# UWB3000.net
KiCad netlist of a schematic drawn in Altium Designer
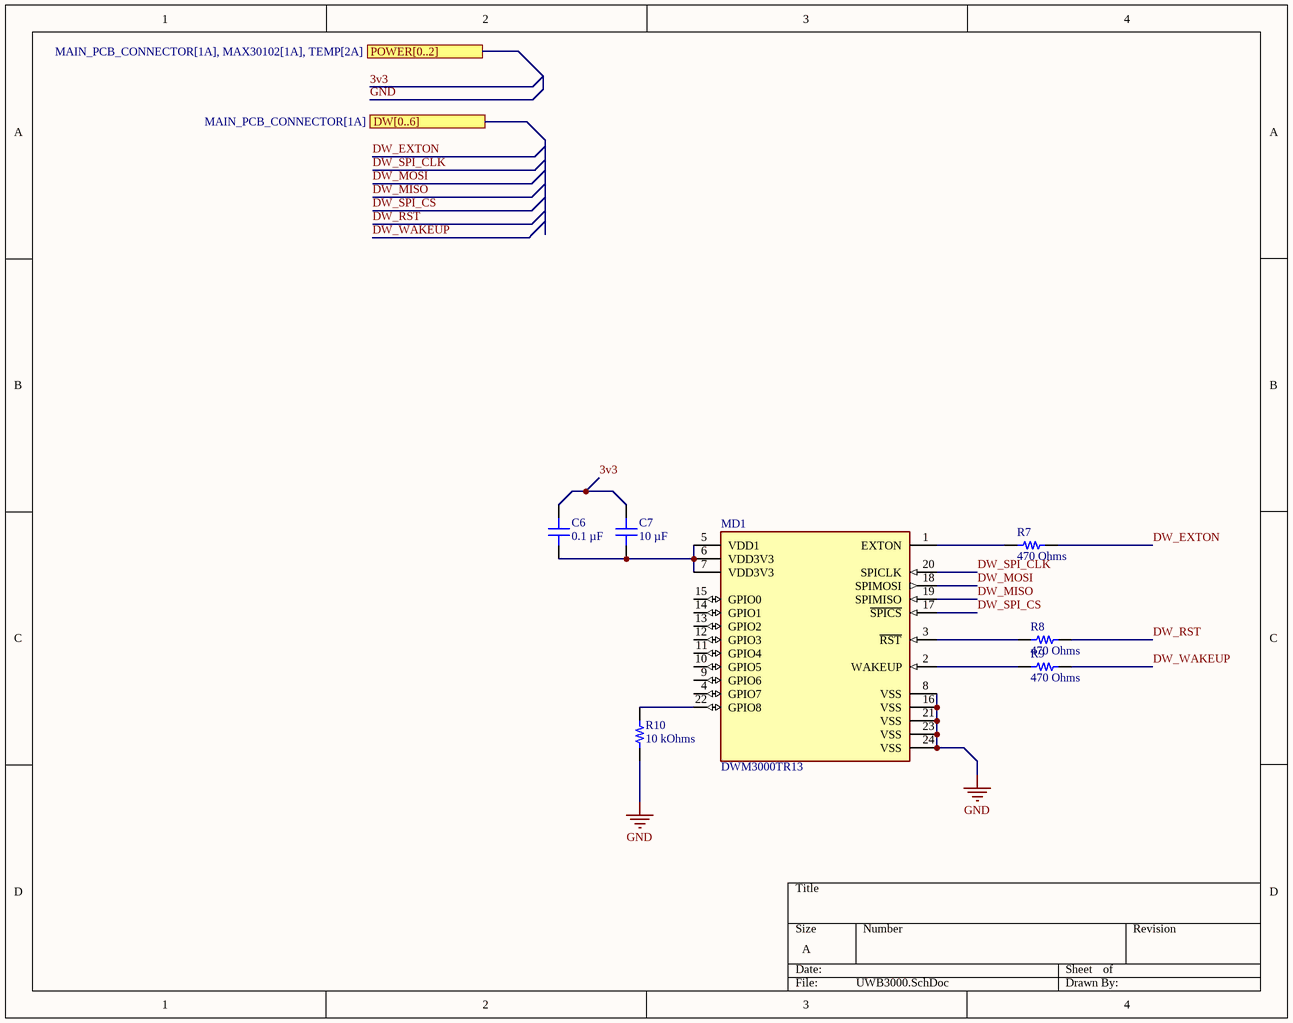
[diagram p0: UWB3000.SchDoc]

(export (version "E")
  (design (tool "Eeschema 10.0.6"))
  (components
    (comp (ref "C6")
      (value "~")
      (footprint "CAP 0402_1005")
      (description "CAP CER 0.1UF 16V X7R 0402")
      (fields
        (field (name "CAPACITANCE") "0.1 µF")
        (field (name "MANUFACTURER") "Samsung Electro-Mechanics")
        (field (name "MFR.PART #") "CL05B104KO5NNNC")
      )
      (libsource (lib "Celestial Altium Library - altium_library") (part "Capacitor"))
    )
    (comp (ref "C7")
      (value "~")
      (footprint "CAP 0402_1005")
      (description "CAP CER 10UF 6.3V X5R 0402")
      (fields
        (field (name "CAPACITANCE") "10 µF")
        (field (name "MANUFACTURER") "Samsung Electro-Mechanics")
        (field (name "MFR.PART #") "CL05A106MQ5NUNC")
      )
      (libsource (lib "Celestial Altium Library - altium_library") (part "Capacitor"))
    )
    (comp (ref "MD1")
      (value "DWM3000TR13")
      (footprint "FP-DWM3000TR13-MFG")
      (description "DWM3000 module Freq: 7.9872 GHz 6.8Mbps SPI 2.5-3.6V 8 GPIO's")
      (fields (field (name "MANUFACTURER") "Qorvo") (field (name "JLCPCB PART #") "C5299931"))
      (libsource (lib "Altium Content Vault") (part "094cfe914922597e69cd10df7811a9c"))
    )
    (comp (ref "R7")
      (value "470 Ohms")
      (footprint "RES 0402_1005")
      (description "RES 470 OHM 0.1% 1/16W 0402")
      (fields
        (field (name "MANUFACTURER") "UNI-ROYAL(Uniroyal Elec)")
        (field (name "MFR.PART #") "0402WGF4700TCE")
      )
      (libsource (lib "Celestial Altium Library - altium_library") (part "Resistor"))
    )
    (comp (ref "R8")
      (value "470 Ohms")
      (footprint "RES 0402_1005")
      (description "RES 470 OHM 0.1% 1/16W 0402")
      (fields
        (field (name "MANUFACTURER") "UNI-ROYAL(Uniroyal Elec)")
        (field (name "MFR.PART #") "0402WGF4700TCE")
      )
      (libsource (lib "Celestial Altium Library - altium_library") (part "Resistor"))
    )
    (comp (ref "R9")
      (value "470 Ohms")
      (footprint "RES 0402_1005")
      (description "RES 470 OHM 0.1% 1/16W 0402")
      (fields
        (field (name "MANUFACTURER") "UNI-ROYAL(Uniroyal Elec)")
        (field (name "MFR.PART #") "0402WGF4700TCE")
      )
      (libsource (lib "Celestial Altium Library - altium_library") (part "Resistor"))
    )
    (comp (ref "R10")
      (value "10 kOhms")
      (footprint "RES 0402_1005")
      (description "RES 10K OHM 0.1% 1/10W 0402")
      (fields (field (name "MANUFACTURER") "Ever Ohms Tech") (field (name "MFR.PART #") "TR0402D10K0Q1025Z"))
      (libsource (lib "Celestial Altium Library - altium_library") (part "Resistor"))
    )
  )
  (nets
    (net (code "11") (name "/3v3") (class "Default")
      (node (ref "C6") (pin "2") (pinfunction "2_2") (pintype "passive"))
      (node (ref "C7") (pin "2") (pinfunction "2_2") (pintype "passive"))
    )
    (net (code "13") (name "/DW_EXTON") (class "Default")
      (node (ref "R7") (pin "2") (pinfunction "2_2") (pintype "passive"))
    )
    (net (code "14") (name "/DW_MISO") (class "Default")
      (node (ref "MD1") (pin "19") (pinfunction "SPIMISO_19") (pintype "input"))
    )
    (net (code "15") (name "/DW_MOSI") (class "Default")
      (node (ref "MD1") (pin "18") (pinfunction "SPIMOSI_18") (pintype "output"))
    )
    (net (code "16") (name "/DW_RST") (class "Default")
      (node (ref "R8") (pin "2") (pinfunction "2_2") (pintype "passive"))
    )
    (net (code "17") (name "/DW_SPI_CLK") (class "Default")
      (node (ref "MD1") (pin "20") (pinfunction "SPICLK_20") (pintype "input"))
    )
    (net (code "18") (name "/DW_SPI_CS") (class "Default")
      (node (ref "MD1") (pin "17") (pinfunction "~{SPICS}_17") (pintype "input"))
    )
    (net (code "19") (name "/DW_WAKEUP") (class "Default")
      (node (ref "R9") (pin "2") (pinfunction "2_2") (pintype "passive"))
    )
    (net (code "21") (name "GND") (class "Default")
      (node (ref "MD1") (pin "16") (pinfunction "VSS_16") (pintype "power_in"))
      (node (ref "MD1") (pin "21") (pinfunction "VSS_21") (pintype "power_in"))
      (node (ref "MD1") (pin "23") (pinfunction "VSS_23") (pintype "power_in"))
      (node (ref "MD1") (pin "24") (pinfunction "VSS_24") (pintype "power_in"))
      (node (ref "MD1") (pin "8") (pinfunction "VSS_8") (pintype "power_in"))
      (node (ref "R10") (pin "1") (pinfunction "1_1") (pintype "passive"))
    )
    (net (code "22") (name "Net-(MD1-EXTON)") (class "Default")
      (node (ref "MD1") (pin "1") (pinfunction "EXTON_1") (pintype "passive"))
      (node (ref "R7") (pin "1") (pinfunction "1_1") (pintype "passive"))
    )
    (net (code "23") (name "Net-(MD1-GPIO8)") (class "Default")
      (node (ref "MD1") (pin "22") (pinfunction "GPIO8_22") (pintype "bidirectional"))
      (node (ref "R10") (pin "2") (pinfunction "2_2") (pintype "passive"))
    )
    (net (code "24") (name "Net-(MD1-VDD1)") (class "Default")
      (node (ref "C6") (pin "1") (pinfunction "1_1") (pintype "passive"))
      (node (ref "C7") (pin "1") (pinfunction "1_1") (pintype "passive"))
      (node (ref "MD1") (pin "5") (pinfunction "VDD1_5") (pintype "power_in"))
      (node (ref "MD1") (pin "6") (pinfunction "VDD3V3_6") (pintype "power_in"))
      (node (ref "MD1") (pin "7") (pinfunction "VDD3V3_7") (pintype "power_in"))
    )
    (net (code "25") (name "Net-(MD1-WAKEUP)") (class "Default")
      (node (ref "MD1") (pin "2") (pinfunction "WAKEUP_2") (pintype "input"))
      (node (ref "R9") (pin "1") (pinfunction "1_1") (pintype "passive"))
    )
    (net (code "26") (name "Net-(MD1-~{RST})") (class "Default")
      (node (ref "MD1") (pin "3") (pinfunction "~{RST}_3") (pintype "input"))
      (node (ref "R8") (pin "1") (pinfunction "1_1") (pintype "passive"))
    )
    (net (code "27") (name "unconnected-(MD1-GPIO0-Pad15)") (class "Default")
      (node (ref "MD1") (pin "15") (pinfunction "GPIO0_15") (pintype "bidirectional"))
    )
    (net (code "28") (name "unconnected-(MD1-GPIO1-Pad14)") (class "Default")
      (node (ref "MD1") (pin "14") (pinfunction "GPIO1_14") (pintype "bidirectional"))
    )
    (net (code "29") (name "unconnected-(MD1-GPIO2-Pad13)") (class "Default")
      (node (ref "MD1") (pin "13") (pinfunction "GPIO2_13") (pintype "bidirectional"))
    )
    (net (code "30") (name "unconnected-(MD1-GPIO3-Pad12)") (class "Default")
      (node (ref "MD1") (pin "12") (pinfunction "GPIO3_12") (pintype "bidirectional"))
    )
    (net (code "31") (name "unconnected-(MD1-GPIO4-Pad11)") (class "Default")
      (node (ref "MD1") (pin "11") (pinfunction "GPIO4_11") (pintype "bidirectional"))
    )
    (net (code "32") (name "unconnected-(MD1-GPIO5-Pad10)") (class "Default")
      (node (ref "MD1") (pin "10") (pinfunction "GPIO5_10") (pintype "bidirectional"))
    )
    (net (code "33") (name "unconnected-(MD1-GPIO6-Pad9)") (class "Default")
      (node (ref "MD1") (pin "9") (pinfunction "GPIO6_9") (pintype "bidirectional"))
    )
    (net (code "34") (name "unconnected-(MD1-GPIO7-Pad4)") (class "Default")
      (node (ref "MD1") (pin "4") (pinfunction "GPIO7_4") (pintype "bidirectional"))
    )
  )
)
